# Segger_JTAG.net
KiCad netlist of a schematic drawn in EAGLE
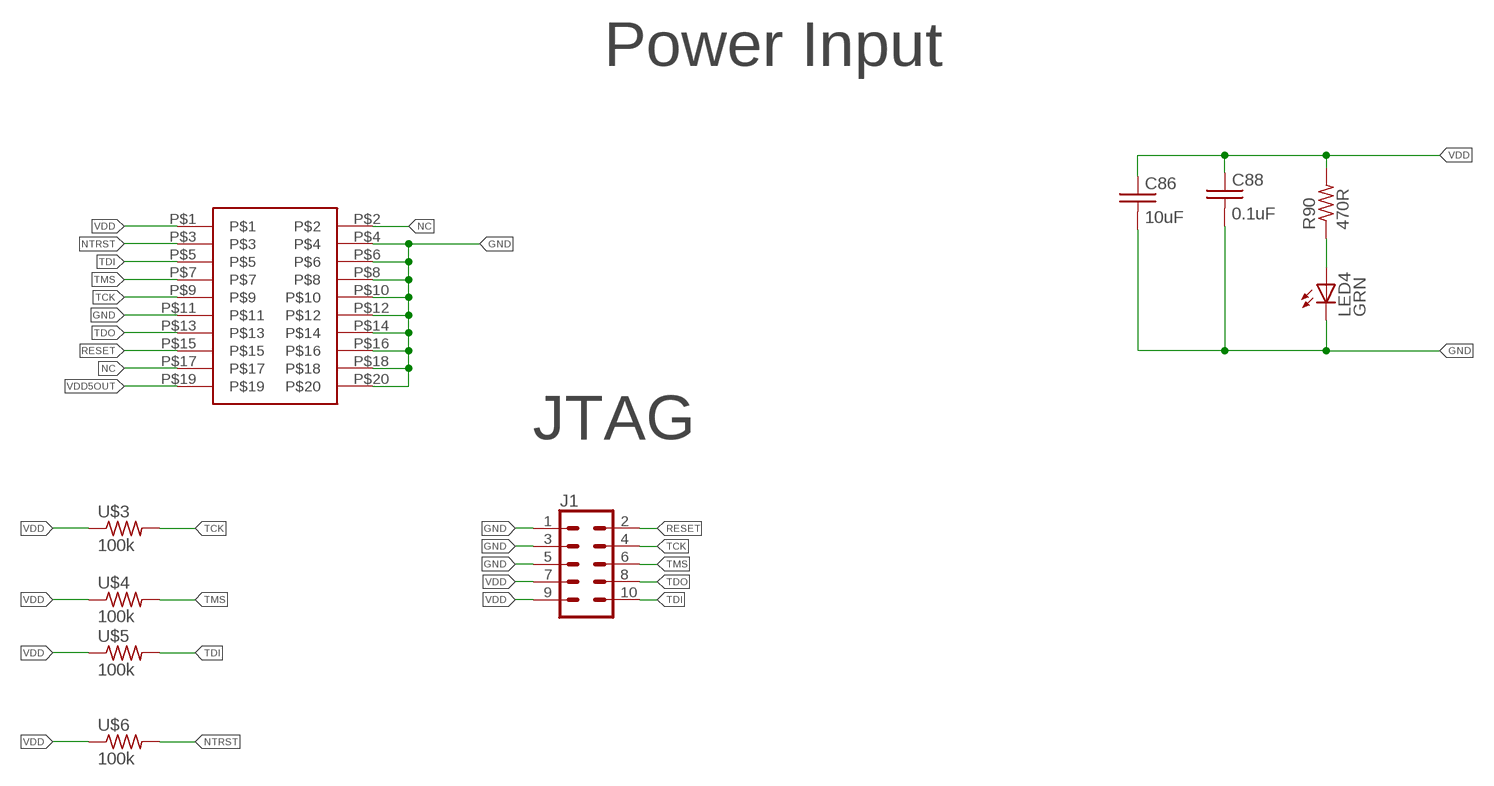
[diagram p0: schematic, sheet 1]

(export (version "E")
  (design (tool "Eeschema 10.0.6"))
  (components
    (comp (ref "C86")
      (value "10uF")
      (footprint "eagle-import:0805")
      (libsource (lib "eagle-import") (part "C_0805"))
    )
    (comp (ref "C88")
      (value "0.1uF")
      (footprint "eagle-import:0805")
      (libsource (lib "eagle-import") (part "C_0805"))
    )
    (comp (ref "J1")
      (value "CONN_05X2SHD")
      (footprint "eagle-import:2X5-SHROUDED")
      (libsource (lib "eagle-import") (part "CONN_05X2SHD"))
    )
    (comp (ref "LED4")
      (value "LED_0805_GREEN")
      (footprint "eagle-import:LED_0805_GREEN")
      (libsource (lib "eagle-import") (part "LED_0805_GREEN"))
    )
    (comp (ref "R90")
      (value "470R")
      (footprint "eagle-import:0805")
      (libsource (lib "eagle-import") (part "R_0805"))
    )
    (comp (ref "U$2")
      (value "2_X_10_HEADER_GENERIC")
      (footprint "eagle-import:2_X_10_.1_INCH")
      (libsource (lib "eagle-import") (part "2_X_10_HEADER_GENERIC"))
    )
    (comp (ref "U$3")
      (value "100k")
      (footprint "eagle-import:0805")
      (libsource (lib "eagle-import") (part "R_0805"))
    )
    (comp (ref "U$4")
      (value "100k")
      (footprint "eagle-import:0805")
      (libsource (lib "eagle-import") (part "R_0805"))
    )
    (comp (ref "U$5")
      (value "100k")
      (footprint "eagle-import:0805")
      (libsource (lib "eagle-import") (part "R_0805"))
    )
    (comp (ref "U$6")
      (value "100k")
      (footprint "eagle-import:0805")
      (libsource (lib "eagle-import") (part "R_0805"))
    )
  )
  (nets
    (net (code "1") (name "GND") (class "Default")
      (node (ref "C86") (pin "2") (pinfunction "2_2") (pintype "passive"))
      (node (ref "C88") (pin "2") (pinfunction "2_2") (pintype "passive"))
      (node (ref "J1") (pin "1") (pinfunction "1_1") (pintype "passive"))
      (node (ref "J1") (pin "3") (pinfunction "3_3") (pintype "passive"))
      (node (ref "J1") (pin "5") (pinfunction "5_5") (pintype "passive"))
      (node (ref "LED4") (pin "C") (pinfunction "C_C") (pintype "passive"))
      (node (ref "U$2") (pin "P$10") (pinfunction "P$10_P$10") (pintype "bidirectional"))
      (node (ref "U$2") (pin "P$11") (pinfunction "P$11_P$11") (pintype "bidirectional"))
      (node (ref "U$2") (pin "P$12") (pinfunction "P$12_P$12") (pintype "bidirectional"))
      (node (ref "U$2") (pin "P$14") (pinfunction "P$14_P$14") (pintype "bidirectional"))
      (node (ref "U$2") (pin "P$16") (pinfunction "P$16_P$16") (pintype "bidirectional"))
      (node (ref "U$2") (pin "P$18") (pinfunction "P$18_P$18") (pintype "bidirectional"))
      (node (ref "U$2") (pin "P$20") (pinfunction "P$20_P$20") (pintype "bidirectional"))
      (node (ref "U$2") (pin "P$4") (pinfunction "P$4_P$4") (pintype "bidirectional"))
      (node (ref "U$2") (pin "P$6") (pinfunction "P$6_P$6") (pintype "bidirectional"))
      (node (ref "U$2") (pin "P$8") (pinfunction "P$8_P$8") (pintype "bidirectional"))
    )
    (net (code "2") (name "NC") (class "Default")
      (node (ref "U$2") (pin "P$17") (pinfunction "P$17_P$17") (pintype "bidirectional"))
      (node (ref "U$2") (pin "P$2") (pinfunction "P$2_P$2") (pintype "bidirectional"))
    )
    (net (code "3") (name "NTRST") (class "Default")
      (node (ref "U$2") (pin "P$3") (pinfunction "P$3_P$3") (pintype "bidirectional"))
      (node (ref "U$6") (pin "2") (pinfunction "2_2") (pintype "passive"))
    )
    (net (code "4") (name "Net-(LED4-PadA)") (class "Default")
      (node (ref "LED4") (pin "A") (pinfunction "A_A") (pintype "passive"))
      (node (ref "R90") (pin "1") (pinfunction "1_1") (pintype "passive"))
    )
    (net (code "5") (name "RESET") (class "Default")
      (node (ref "J1") (pin "2") (pinfunction "2_2") (pintype "passive"))
      (node (ref "U$2") (pin "P$15") (pinfunction "P$15_P$15") (pintype "bidirectional"))
    )
    (net (code "6") (name "TCK") (class "Default")
      (node (ref "J1") (pin "4") (pinfunction "4_4") (pintype "passive"))
      (node (ref "U$2") (pin "P$9") (pinfunction "P$9_P$9") (pintype "bidirectional"))
      (node (ref "U$3") (pin "2") (pinfunction "2_2") (pintype "passive"))
    )
    (net (code "7") (name "TDI") (class "Default")
      (node (ref "J1") (pin "10") (pinfunction "10_10") (pintype "passive"))
      (node (ref "U$2") (pin "P$5") (pinfunction "P$5_P$5") (pintype "bidirectional"))
      (node (ref "U$5") (pin "2") (pinfunction "2_2") (pintype "passive"))
    )
    (net (code "8") (name "TDO") (class "Default")
      (node (ref "J1") (pin "8") (pinfunction "8_8") (pintype "passive"))
      (node (ref "U$2") (pin "P$13") (pinfunction "P$13_P$13") (pintype "bidirectional"))
    )
    (net (code "9") (name "TMS") (class "Default")
      (node (ref "J1") (pin "6") (pinfunction "6_6") (pintype "passive"))
      (node (ref "U$2") (pin "P$7") (pinfunction "P$7_P$7") (pintype "bidirectional"))
      (node (ref "U$4") (pin "2") (pinfunction "2_2") (pintype "passive"))
    )
    (net (code "10") (name "VDD") (class "Default")
      (node (ref "C86") (pin "1") (pinfunction "1_1") (pintype "passive"))
      (node (ref "C88") (pin "1") (pinfunction "1_1") (pintype "passive"))
      (node (ref "J1") (pin "7") (pinfunction "7_7") (pintype "passive"))
      (node (ref "J1") (pin "9") (pinfunction "9_9") (pintype "passive"))
      (node (ref "R90") (pin "2") (pinfunction "2_2") (pintype "passive"))
      (node (ref "U$2") (pin "P$1") (pinfunction "P$1_P$1") (pintype "bidirectional"))
      (node (ref "U$3") (pin "1") (pinfunction "1_1") (pintype "passive"))
      (node (ref "U$4") (pin "1") (pinfunction "1_1") (pintype "passive"))
      (node (ref "U$5") (pin "1") (pinfunction "1_1") (pintype "passive"))
      (node (ref "U$6") (pin "1") (pinfunction "1_1") (pintype "passive"))
    )
    (net (code "11") (name "VDD5OUT") (class "Default")
      (node (ref "U$2") (pin "P$19") (pinfunction "P$19_P$19") (pintype "bidirectional"))
    )
  )
)
